# Chocolate3Pi.net
KiCad netlist of a schematic drawn in EAGLE
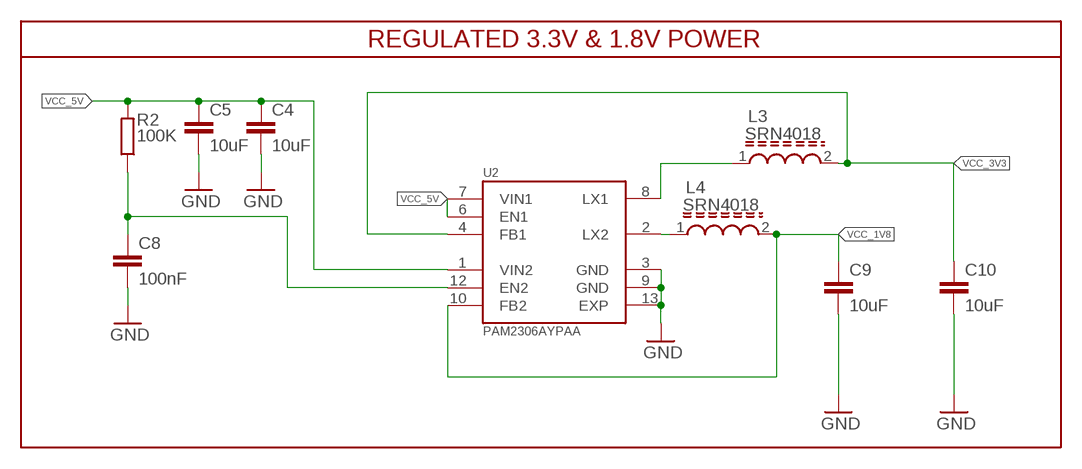
[diagram p0: schematic, sheet 1]

(export (version "E")
  (design (tool "Eeschema 10.0.6"))
  (components
    (comp (ref "C4")
      (value "10uF")
      (footprint "eagle-import:C0805")
      (libsource (lib "eagle-import") (part "C-EUC0805"))
    )
    (comp (ref "C5")
      (value "10uF")
      (footprint "eagle-import:C0805")
      (libsource (lib "eagle-import") (part "C-EUC0805"))
    )
    (comp (ref "C8")
      (value "100nF")
      (footprint "eagle-import:C0603")
      (libsource (lib "eagle-import") (part "C-EUC0603"))
    )
    (comp (ref "C9")
      (value "10uF")
      (footprint "eagle-import:C0805")
      (libsource (lib "eagle-import") (part "C-EUC0805"))
    )
    (comp (ref "C10")
      (value "10uF")
      (footprint "eagle-import:C0805")
      (libsource (lib "eagle-import") (part "C-EUC0805"))
    )
    (comp (ref "L3")
      (value "SRN4018")
      (footprint "eagle-import:INDP4040X180N")
      (libsource (lib "eagle-import") (part "SRN4018"))
    )
    (comp (ref "L4")
      (value "SRN4018")
      (footprint "eagle-import:INDP4040X180N")
      (libsource (lib "eagle-import") (part "SRN4018"))
    )
    (comp (ref "R2")
      (value "100K")
      (footprint "eagle-import:R0603")
      (libsource (lib "eagle-import") (part "R-EU_R0603"))
    )
    (comp (ref "U2")
      (value "PAM2306AYPAA")
      (footprint "eagle-import:SON45P300X300X80-13N")
      (fields (field (name "MF") "Diodes Inc."))
      (libsource (lib "eagle-import") (part "PAM2306AYPAA"))
    )
  )
  (nets
    (net (code "1") (name "GND") (class "Default")
      (node (ref "C10") (pin "2") (pinfunction "2_2") (pintype "passive"))
      (node (ref "C4") (pin "2") (pinfunction "2_2") (pintype "passive"))
      (node (ref "C5") (pin "2") (pinfunction "2_2") (pintype "passive"))
      (node (ref "C8") (pin "2") (pinfunction "2_2") (pintype "passive"))
      (node (ref "C9") (pin "2") (pinfunction "2_2") (pintype "passive"))
      (node (ref "U2") (pin "13") (pinfunction "EXP_13") (pintype "power_in"))
      (node (ref "U2") (pin "3") (pinfunction "GND_3") (pintype "power_in"))
      (node (ref "U2") (pin "9") (pinfunction "GND_9") (pintype "power_in"))
    )
    (net (code "2") (name "Net-(U2-EN2)") (class "Default")
      (node (ref "C8") (pin "1") (pinfunction "1_1") (pintype "passive"))
      (node (ref "R2") (pin "1") (pinfunction "1_1") (pintype "passive"))
      (node (ref "U2") (pin "12") (pinfunction "EN2_12") (pintype "input"))
    )
    (net (code "3") (name "Net-(U2-LX1)") (class "Default")
      (node (ref "L3") (pin "1") (pinfunction "1_1") (pintype "passive"))
      (node (ref "U2") (pin "8") (pinfunction "LX1_8") (pintype "output"))
    )
    (net (code "4") (name "Net-(U2-LX2)") (class "Default")
      (node (ref "L4") (pin "1") (pinfunction "1_1") (pintype "passive"))
      (node (ref "U2") (pin "2") (pinfunction "LX2_2") (pintype "output"))
    )
    (net (code "5") (name "VCC_1V8") (class "Default")
      (node (ref "C9") (pin "1") (pinfunction "1_1") (pintype "passive"))
      (node (ref "L4") (pin "2") (pinfunction "2_2") (pintype "passive"))
      (node (ref "U2") (pin "10") (pinfunction "FB2_10") (pintype "input"))
    )
    (net (code "6") (name "VCC_3V3") (class "Default")
      (node (ref "C10") (pin "1") (pinfunction "1_1") (pintype "passive"))
      (node (ref "L3") (pin "2") (pinfunction "2_2") (pintype "passive"))
      (node (ref "U2") (pin "4") (pinfunction "FB1_4") (pintype "input"))
    )
    (net (code "7") (name "VCC_5V") (class "Default")
      (node (ref "C4") (pin "1") (pinfunction "1_1") (pintype "passive"))
      (node (ref "C5") (pin "1") (pinfunction "1_1") (pintype "passive"))
      (node (ref "R2") (pin "2") (pinfunction "2_2") (pintype "passive"))
      (node (ref "U2") (pin "1") (pinfunction "VIN2_1") (pintype "input"))
      (node (ref "U2") (pin "6") (pinfunction "EN1_6") (pintype "input"))
      (node (ref "U2") (pin "7") (pinfunction "VIN1_7") (pintype "input"))
    )
  )
)
